# SCH_smart_switch_2021-09-12.net
KiCad netlist of a schematic drawn in EasyEDA
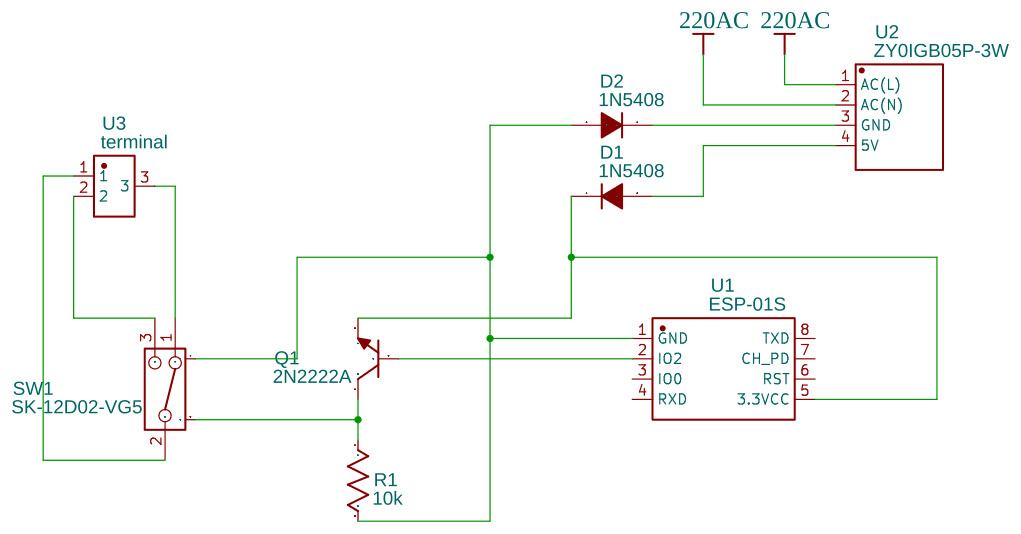
[diagram p0: schematic sheet]

(export (version "E")
  (design (tool "Eeschema 10.0.6"))
  (components
    (comp (ref "D1")
      (value "1N5408")
      (fields (field (name "BOM_Supplier Part") "C87459"))
      (libsource (lib "") (part "1N5408_1"))
    )
    (comp (ref "D2")
      (value "1N5408")
      (fields (field (name "BOM_Supplier Part") "C87459"))
      (libsource (lib "") (part "1N5408"))
    )
    (comp (ref "Q1")
      (value "2N2222A")
      (fields (field (name "BOM_Supplier Part") "C358533"))
      (libsource (lib "") (part "2N2222A"))
    )
    (comp (ref "R1") (value "10k") (libsource (lib "") (part "R_0603_US")))
    (comp (ref "SW1")
      (value "SK-12D02-VG5")
      (fields (field (name "BOM_Supplier Part") "C136722"))
      (libsource (lib "") (part "SK-12D02-VG5"))
    )
    (comp (ref "U1")
      (value "ESP-01S")
      (fields (field (name "BOM_Supplier Part") "C111009"))
      (libsource (lib "") (part "ESP-01S"))
    )
    (comp (ref "U2")
      (value "ZY0IGB05P-3W")
      (fields (field (name "BOM_Supplier Part") "C85698"))
      (libsource (lib "") (part "ZY0IGB05P-3W"))
    )
    (comp (ref "U3")
      (value "terminal")
      (fields
        (field (name "BOM_Manufacturer Part") "2.54-3P接线端子")
        (field (name "BOM_Supplier Part") "C68305")
      )
      (libsource (lib "") (part "2.54-3P接线端子"))
    )
  )
  (nets
    (net (code "1") (name "220AC") (class "Default")
      (node (ref "U2") (pin "1") (pinfunction "AC(L)_1") (pintype "unspecified"))
      (node (ref "U2") (pin "2") (pinfunction "AC(N)_2") (pintype "unspecified"))
    )
    (net (code "2") (name "Net-(D1-A)") (class "Default")
      (node (ref "D1") (pin "2") (pinfunction "A_2") (pintype "unspecified"))
      (node (ref "U2") (pin "4") (pinfunction "5V_4") (pintype "unspecified"))
    )
    (net (code "3") (name "Net-(D1-K)") (class "Default")
      (node (ref "D1") (pin "1") (pinfunction "K_1") (pintype "unspecified"))
      (node (ref "Q1") (pin "3") (pinfunction "E_3") (pintype "unspecified"))
      (node (ref "U1") (pin "5") (pinfunction "3.3VCC_5") (pintype "unspecified"))
    )
    (net (code "4") (name "Net-(D2-A)") (class "Default")
      (node (ref "D2") (pin "2") (pinfunction "A_2") (pintype "unspecified"))
      (node (ref "R1") (pin "2") (pinfunction "2_2") (pintype "unspecified"))
      (node (ref "SW1") (pin "4") (pinfunction "4_4") (pintype "unspecified"))
      (node (ref "U1") (pin "1") (pinfunction "GND_1") (pintype "unspecified"))
    )
    (net (code "5") (name "Net-(D2-K)") (class "Default")
      (node (ref "D2") (pin "1") (pinfunction "K_1") (pintype "unspecified"))
      (node (ref "U2") (pin "3") (pinfunction "GND_3") (pintype "unspecified"))
    )
    (net (code "6") (name "Net-(Q1-B)") (class "Default")
      (node (ref "Q1") (pin "2") (pinfunction "B_2") (pintype "unspecified"))
      (node (ref "U1") (pin "2") (pinfunction "IO2_2") (pintype "unspecified"))
    )
    (net (code "7") (name "Net-(Q1-C)") (class "Default")
      (node (ref "Q1") (pin "1") (pinfunction "C_1") (pintype "unspecified"))
      (node (ref "R1") (pin "1") (pinfunction "1_1") (pintype "unspecified"))
      (node (ref "SW1") (pin "5") (pinfunction "5_5") (pintype "unspecified"))
    )
    (net (code "8") (name "Net-(SW1-Pad1)") (class "Default")
      (node (ref "SW1") (pin "1") (pinfunction "1_1") (pintype "unspecified"))
      (node (ref "U3") (pin "3") (pinfunction "3_3") (pintype "unspecified"))
    )
    (net (code "9") (name "Net-(SW1-Pad2)") (class "Default")
      (node (ref "SW1") (pin "2") (pinfunction "2_2") (pintype "unspecified"))
      (node (ref "U3") (pin "1") (pinfunction "1_1") (pintype "unspecified"))
    )
    (net (code "10") (name "Net-(SW1-Pad3)") (class "Default")
      (node (ref "SW1") (pin "3") (pinfunction "3_3") (pintype "unspecified"))
      (node (ref "U3") (pin "2") (pinfunction "2_2") (pintype "unspecified"))
    )
    (net (code "11") (name "unconnected-(U1-CH_PD-Pad7)") (class "Default")
      (node (ref "U1") (pin "7") (pinfunction "CH_PD_7") (pintype "unspecified"))
    )
    (net (code "12") (name "unconnected-(U1-IO0-Pad3)") (class "Default")
      (node (ref "U1") (pin "3") (pinfunction "IO0_3") (pintype "unspecified"))
    )
    (net (code "13") (name "unconnected-(U1-RST-Pad6)") (class "Default")
      (node (ref "U1") (pin "6") (pinfunction "RST_6") (pintype "unspecified"))
    )
    (net (code "14") (name "unconnected-(U1-RXD-Pad4)") (class "Default")
      (node (ref "U1") (pin "4") (pinfunction "RXD_4") (pintype "unspecified"))
    )
    (net (code "15") (name "unconnected-(U1-TXD-Pad8)") (class "Default")
      (node (ref "U1") (pin "8") (pinfunction "TXD_8") (pintype "unspecified"))
    )
  )
)
